# sbcs.net
KiCad netlist of a schematic drawn in Altium Designer
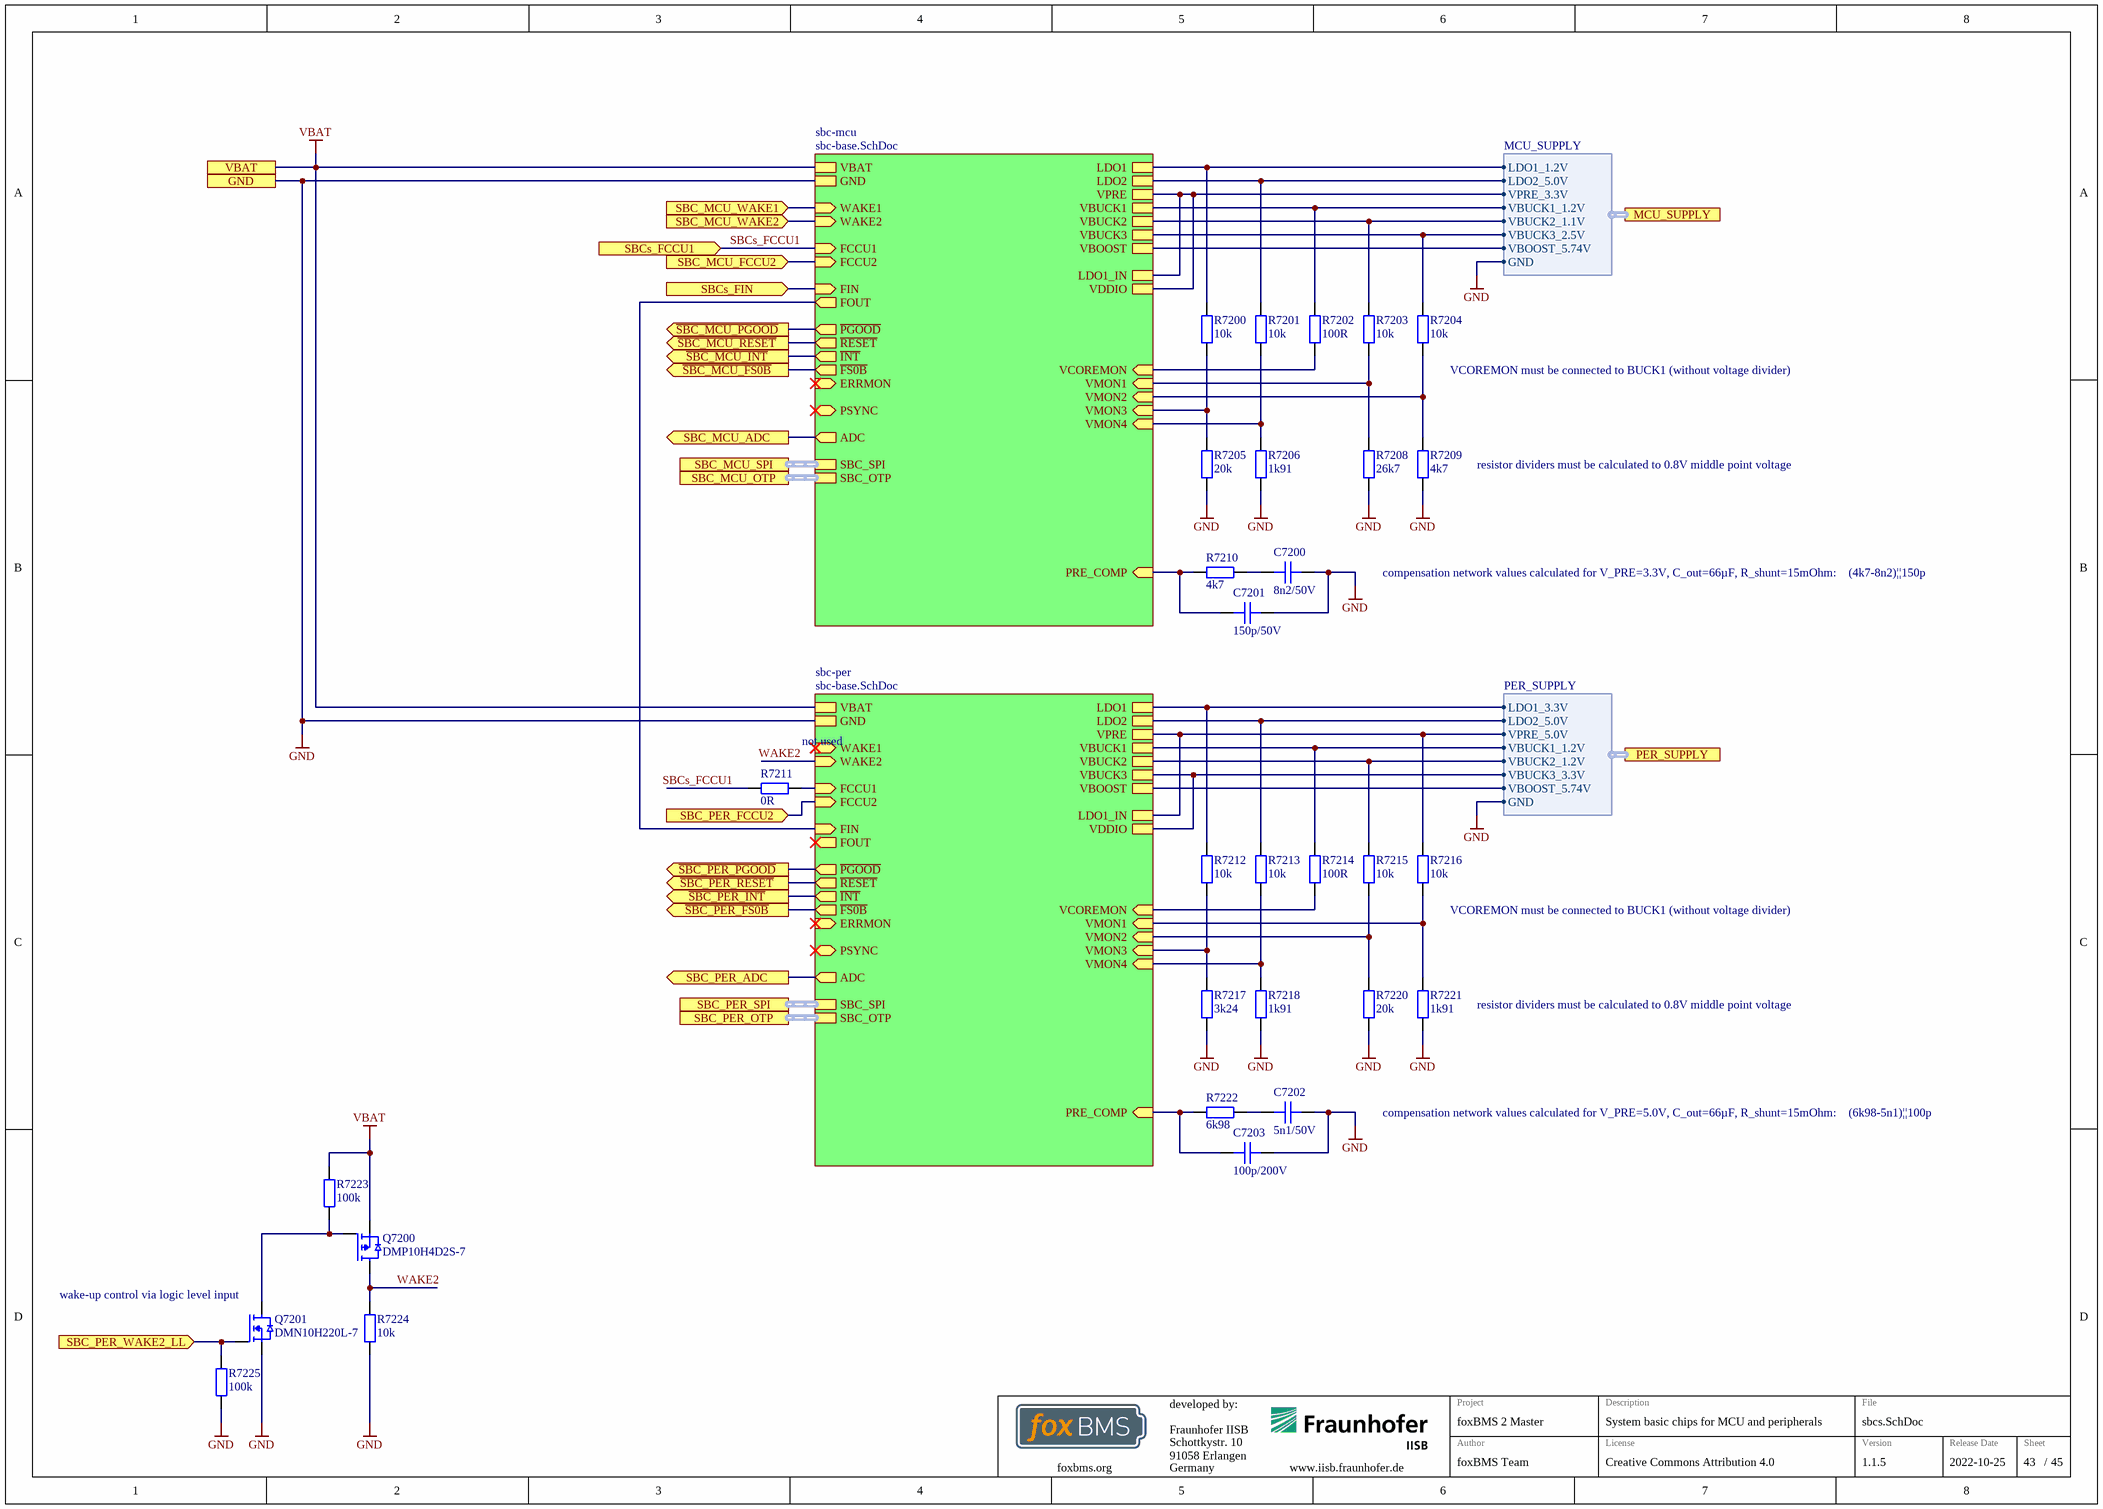
[diagram p0: sbcs.SchDoc]

(export (version "E")
  (design (tool "Eeschema 10.0.6"))
  (components
    (comp (ref "C7200")
      (value "8n2/50V")
      (footprint "CAPC1608X08N")
      (description "MLCC")
      (fields (field (name "PART NUMBER") "gen_C_ceramic_8n2_50V_C0G_0603"))
      (libsource (lib "OE750") (part "C"))
    )
    (comp (ref "C7201")
      (value "150p/50V")
      (footprint "CAPC1005X06N")
      (description "MLCC")
      (fields (field (name "PART NUMBER") "gen_C_ceramic_150p_50V_C0G_0402"))
      (libsource (lib "OE750") (part "C"))
    )
    (comp (ref "C7202")
      (value "5n1/50V")
      (footprint "CAPC1608X08N")
      (description "MLCC")
      (fields (field (name "PART NUMBER") "gen_C_ceramic_5n1_50V_C0G_0603"))
      (libsource (lib "OE750") (part "C"))
    )
    (comp (ref "C7203")
      (value "100p/200V")
      (footprint "CAPC1005X06N")
      (description "MLCC")
      (fields (field (name "PART NUMBER") "gen_C_ceramic_100p_200V_C0G_0402") (field (name "TOLERANCE") "5%"))
      (libsource (lib "OE750") (part "C"))
    )
    (comp (ref "Q7200")
      (value "DMP10H4D2S-7")
      (footprint "SOT95P237X110-3N")
      (description "MOSFET-Transistor, p-Kanal, 0.27 A, 100 V, 4.2 ohm")
      (fields (field (name "MANUFACTURER") "Diodes"))
      (libsource (lib "OE750") (part "PMOS"))
    )
    (comp (ref "Q7201")
      (value "DMN10H220L-7")
      (footprint "SOT95P237X110-3N")
      (description "MOSFET-Transistor, n-Kanal, 1.6 A, 100 V, 0.250 ohm")
      (fields (field (name "MANUFACTURER") "Diodes"))
      (libsource (lib "OE750") (part "NMOS"))
    )
    (comp (ref "R7200")
      (value "10k")
      (footprint "RESC1005X04N")
      (description "SMD Resistor 10k 0402")
      (fields (field (name "PART NUMBER") "gen_R_10k_0402") (field (name "TOLERANCE") "1%"))
      (libsource (lib "OE750") (part "R"))
    )
    (comp (ref "R7201")
      (value "10k")
      (footprint "RESC1005X04N")
      (description "SMD Resistor 10k 0402")
      (fields (field (name "PART NUMBER") "gen_R_10k_0402") (field (name "TOLERANCE") "1%"))
      (libsource (lib "OE750") (part "R"))
    )
    (comp (ref "R7202")
      (value "100R")
      (footprint "RESC1005X04N")
      (description "SMD Resistor 100R 0402")
      (fields (field (name "PART NUMBER") "gen_R_100R_0402") (field (name "TOLERANCE") "1%"))
      (libsource (lib "OE750") (part "R"))
    )
    (comp (ref "R7203")
      (value "10k")
      (footprint "RESC1005X04N")
      (description "SMD Resistor 10k 0402")
      (fields (field (name "PART NUMBER") "gen_R_10k_0402") (field (name "TOLERANCE") "1%"))
      (libsource (lib "OE750") (part "R"))
    )
    (comp (ref "R7204")
      (value "10k")
      (footprint "RESC1005X04N")
      (description "SMD Resistor 10k 0402")
      (fields (field (name "PART NUMBER") "gen_R_10k_0402") (field (name "TOLERANCE") "1%"))
      (libsource (lib "OE750") (part "R"))
    )
    (comp (ref "R7205")
      (value "20k")
      (footprint "RESC1005X04N")
      (description "SMD Resistor 20k 0402")
      (fields (field (name "PART NUMBER") "gen_R_20k_0402") (field (name "TOLERANCE") "1%"))
      (libsource (lib "OE750") (part "R"))
    )
    (comp (ref "R7206")
      (value "1k91")
      (footprint "RESC1005X04N")
      (description "SMD Resistor 1k91 0402")
      (fields (field (name "PART NUMBER") "gen_R_1k91_0402") (field (name "TOLERANCE") "1%"))
      (libsource (lib "OE750") (part "R"))
    )
    (comp (ref "R7208")
      (value "26k7")
      (footprint "RESC1005X04N")
      (description "SMD Resistor 26k7 0402")
      (fields (field (name "PART NUMBER") "gen_R_26k7_0402") (field (name "TOLERANCE") "1%"))
      (libsource (lib "OE750") (part "R"))
    )
    (comp (ref "R7209")
      (value "4k7")
      (footprint "RESC1005X04N")
      (description "SMD Resistor 4k7 0402")
      (fields (field (name "PART NUMBER") "gen_R_4k7_0402") (field (name "TOLERANCE") "1%"))
      (libsource (lib "OE750") (part "R"))
    )
    (comp (ref "R7210")
      (value "4k7")
      (footprint "RESC1005X04N")
      (description "SMD Resistor 4k7 0402")
      (fields (field (name "PART NUMBER") "gen_R_4k7_0402") (field (name "TOLERANCE") "1%"))
      (libsource (lib "OE750") (part "R"))
    )
    (comp (ref "R7211")
      (value "0R")
      (footprint "RESC1005X04N")
      (description "SMD Resistor 0R 0402")
      (fields (field (name "PART NUMBER") "gen_R_0R_0402") (field (name "POWER") "0.063W"))
      (libsource (lib "OE750") (part "R"))
    )
    (comp (ref "R7212")
      (value "10k")
      (footprint "RESC1005X04N")
      (description "SMD Resistor 10k 0402")
      (fields (field (name "PART NUMBER") "gen_R_10k_0402") (field (name "TOLERANCE") "1%"))
      (libsource (lib "OE750") (part "R"))
    )
    (comp (ref "R7213")
      (value "10k")
      (footprint "RESC1005X04N")
      (description "SMD Resistor 10k 0402")
      (fields (field (name "PART NUMBER") "gen_R_10k_0402") (field (name "TOLERANCE") "1%"))
      (libsource (lib "OE750") (part "R"))
    )
    (comp (ref "R7214")
      (value "100R")
      (footprint "RESC1005X04N")
      (description "SMD Resistor 100R 0402")
      (fields (field (name "PART NUMBER") "gen_R_100R_0402") (field (name "TOLERANCE") "1%"))
      (libsource (lib "OE750") (part "R"))
    )
    (comp (ref "R7215")
      (value "10k")
      (footprint "RESC1005X04N")
      (description "SMD Resistor 10k 0402")
      (fields (field (name "PART NUMBER") "gen_R_10k_0402") (field (name "TOLERANCE") "1%"))
      (libsource (lib "OE750") (part "R"))
    )
    (comp (ref "R7216")
      (value "10k")
      (footprint "RESC1005X04N")
      (description "SMD Resistor 10k 0402")
      (fields (field (name "PART NUMBER") "gen_R_10k_0402") (field (name "TOLERANCE") "1%"))
      (libsource (lib "OE750") (part "R"))
    )
    (comp (ref "R7217")
      (value "3k24")
      (footprint "RESC1005X04N")
      (description "SMD Resistor 3k24 0402")
      (fields (field (name "PART NUMBER") "gen_R_3k24_0402") (field (name "TOLERANCE") "1%"))
      (libsource (lib "OE750") (part "R"))
    )
    (comp (ref "R7218")
      (value "1k91")
      (footprint "RESC1005X04N")
      (description "SMD Resistor 1k91 0402")
      (fields (field (name "PART NUMBER") "gen_R_1k91_0402") (field (name "TOLERANCE") "1%"))
      (libsource (lib "OE750") (part "R"))
    )
    (comp (ref "R7220")
      (value "20k")
      (footprint "RESC1005X04N")
      (description "SMD Resistor 20k 0402")
      (fields (field (name "PART NUMBER") "gen_R_20k_0402") (field (name "TOLERANCE") "1%"))
      (libsource (lib "OE750") (part "R"))
    )
    (comp (ref "R7221")
      (value "1k91")
      (footprint "RESC1005X04N")
      (description "SMD Resistor 1k91 0402")
      (fields (field (name "PART NUMBER") "gen_R_1k91_0402") (field (name "TOLERANCE") "1%"))
      (libsource (lib "OE750") (part "R"))
    )
    (comp (ref "R7222")
      (value "6k98")
      (footprint "RESC1005X04N")
      (description "SMD Resistor 6k98 0402")
      (fields (field (name "PART NUMBER") "gen_R_6k98_0402") (field (name "TOLERANCE") "1%"))
      (libsource (lib "OE750") (part "R"))
    )
    (comp (ref "R7223")
      (value "100k")
      (footprint "RESC1005X04N")
      (description "SMD Resistor 100k 0402")
      (fields (field (name "PART NUMBER") "gen_R_100k_0402") (field (name "TOLERANCE") "1%"))
      (libsource (lib "OE750") (part "R"))
    )
    (comp (ref "R7224")
      (value "10k")
      (footprint "RESC1005X04N")
      (description "SMD Resistor 10k 0402")
      (fields (field (name "PART NUMBER") "gen_R_10k_0402") (field (name "TOLERANCE") "1%"))
      (libsource (lib "OE750") (part "R"))
    )
    (comp (ref "R7225")
      (value "100k")
      (footprint "RESC1005X04N")
      (description "SMD Resistor 100k 0402")
      (fields (field (name "PART NUMBER") "gen_R_100k_0402") (field (name "TOLERANCE") "1%"))
      (libsource (lib "OE750") (part "R"))
    )
  )
  (nets
    (net (code "9") (name "/FCCU1") (class "Default")
      (node (ref "R7211") (pin "2") (pinfunction "2_2") (pintype "passive"))
    )
    (net (code "12") (name "/LDO1") (class "Default")
      (node (ref "R7212") (pin "2") (pinfunction "2_2") (pintype "passive"))
    )
    (net (code "13") (name "/LDO1_1") (class "Default")
      (node (ref "R7200") (pin "2") (pinfunction "2_2") (pintype "passive"))
    )
    (net (code "14") (name "/LDO1_IN") (class "Default")
      (node (ref "R7216") (pin "2") (pinfunction "2_2") (pintype "passive"))
    )
    (net (code "16") (name "/LDO2") (class "Default")
      (node (ref "R7213") (pin "2") (pinfunction "2_2") (pintype "passive"))
    )
    (net (code "17") (name "/LDO2_1") (class "Default")
      (node (ref "R7201") (pin "2") (pinfunction "2_2") (pintype "passive"))
    )
    (net (code "18") (name "/PRE_COMP") (class "Default")
      (node (ref "C7201") (pin "1") (pinfunction "1_1") (pintype "passive"))
      (node (ref "R7210") (pin "2") (pinfunction "2_2") (pintype "passive"))
    )
    (net (code "19") (name "/PRE_COMP_1") (class "Default")
      (node (ref "C7203") (pin "1") (pinfunction "1_1") (pintype "passive"))
      (node (ref "R7222") (pin "2") (pinfunction "2_2") (pintype "passive"))
    )
    (net (code "40") (name "/SBC_PER_WAKE2_LL") (class "Default")
      (node (ref "Q7201") (pin "G") (pinfunction "G_G") (pintype "passive"))
      (node (ref "R7225") (pin "1") (pinfunction "1_1") (pintype "passive"))
    )
    (net (code "41") (name "/SBCs_FCCU1") (class "Default")
      (node (ref "R7211") (pin "1") (pinfunction "1_1") (pintype "passive"))
    )
    (net (code "45") (name "/VBUCK1") (class "Default")
      (node (ref "R7214") (pin "2") (pinfunction "2_2") (pintype "passive"))
    )
    (net (code "46") (name "/VBUCK1_1") (class "Default")
      (node (ref "R7202") (pin "2") (pinfunction "2_2") (pintype "passive"))
    )
    (net (code "47") (name "/VBUCK2") (class "Default")
      (node (ref "R7215") (pin "2") (pinfunction "2_2") (pintype "passive"))
    )
    (net (code "48") (name "/VBUCK2_1") (class "Default")
      (node (ref "R7203") (pin "2") (pinfunction "2_2") (pintype "passive"))
    )
    (net (code "50") (name "/VBUCK3_1") (class "Default")
      (node (ref "R7204") (pin "2") (pinfunction "2_2") (pintype "passive"))
    )
    (net (code "51") (name "/VCOREMON") (class "Default")
      (node (ref "R7214") (pin "1") (pinfunction "1_1") (pintype "passive"))
    )
    (net (code "52") (name "/VCOREMON_1") (class "Default")
      (node (ref "R7202") (pin "1") (pinfunction "1_1") (pintype "passive"))
    )
    (net (code "53") (name "/VMON1") (class "Default")
      (node (ref "R7216") (pin "1") (pinfunction "1_1") (pintype "passive"))
      (node (ref "R7221") (pin "2") (pinfunction "2_2") (pintype "passive"))
    )
    (net (code "54") (name "/VMON1_1") (class "Default")
      (node (ref "R7203") (pin "1") (pinfunction "1_1") (pintype "passive"))
      (node (ref "R7208") (pin "2") (pinfunction "2_2") (pintype "passive"))
    )
    (net (code "55") (name "/VMON2") (class "Default")
      (node (ref "R7215") (pin "1") (pinfunction "1_1") (pintype "passive"))
      (node (ref "R7220") (pin "2") (pinfunction "2_2") (pintype "passive"))
    )
    (net (code "56") (name "/VMON2_1") (class "Default")
      (node (ref "R7204") (pin "1") (pinfunction "1_1") (pintype "passive"))
      (node (ref "R7209") (pin "2") (pinfunction "2_2") (pintype "passive"))
    )
    (net (code "57") (name "/VMON3") (class "Default")
      (node (ref "R7212") (pin "1") (pinfunction "1_1") (pintype "passive"))
      (node (ref "R7217") (pin "2") (pinfunction "2_2") (pintype "passive"))
    )
    (net (code "58") (name "/VMON3_1") (class "Default")
      (node (ref "R7200") (pin "1") (pinfunction "1_1") (pintype "passive"))
      (node (ref "R7205") (pin "2") (pinfunction "2_2") (pintype "passive"))
    )
    (net (code "59") (name "/VMON4") (class "Default")
      (node (ref "R7213") (pin "1") (pinfunction "1_1") (pintype "passive"))
      (node (ref "R7218") (pin "2") (pinfunction "2_2") (pintype "passive"))
    )
    (net (code "60") (name "/VMON4_1") (class "Default")
      (node (ref "R7201") (pin "1") (pinfunction "1_1") (pintype "passive"))
      (node (ref "R7206") (pin "2") (pinfunction "2_2") (pintype "passive"))
    )
    (net (code "62") (name "/WAKE2") (class "Default")
      (node (ref "Q7200") (pin "D") (pinfunction "D_D") (pintype "passive"))
      (node (ref "R7224") (pin "2") (pinfunction "2_2") (pintype "passive"))
    )
    (net (code "65") (name "GND") (class "Default")
      (node (ref "C7200") (pin "2") (pinfunction "2_2") (pintype "passive"))
      (node (ref "C7201") (pin "2") (pinfunction "2_2") (pintype "passive"))
      (node (ref "C7202") (pin "2") (pinfunction "2_2") (pintype "passive"))
      (node (ref "C7203") (pin "2") (pinfunction "2_2") (pintype "passive"))
      (node (ref "Q7201") (pin "S") (pinfunction "S_S") (pintype "passive"))
      (node (ref "R7205") (pin "1") (pinfunction "1_1") (pintype "passive"))
      (node (ref "R7206") (pin "1") (pinfunction "1_1") (pintype "passive"))
      (node (ref "R7208") (pin "1") (pinfunction "1_1") (pintype "passive"))
      (node (ref "R7209") (pin "1") (pinfunction "1_1") (pintype "passive"))
      (node (ref "R7217") (pin "1") (pinfunction "1_1") (pintype "passive"))
      (node (ref "R7218") (pin "1") (pinfunction "1_1") (pintype "passive"))
      (node (ref "R7220") (pin "1") (pinfunction "1_1") (pintype "passive"))
      (node (ref "R7221") (pin "1") (pinfunction "1_1") (pintype "passive"))
      (node (ref "R7224") (pin "1") (pinfunction "1_1") (pintype "passive"))
      (node (ref "R7225") (pin "2") (pinfunction "2_2") (pintype "passive"))
    )
    (net (code "66") (name "Net-(C7200-Pad1)") (class "Default")
      (node (ref "C7200") (pin "1") (pinfunction "1_1") (pintype "passive"))
      (node (ref "R7210") (pin "1") (pinfunction "1_1") (pintype "passive"))
    )
    (net (code "67") (name "Net-(C7202-Pad1)") (class "Default")
      (node (ref "C7202") (pin "1") (pinfunction "1_1") (pintype "passive"))
      (node (ref "R7222") (pin "1") (pinfunction "1_1") (pintype "passive"))
    )
    (net (code "68") (name "Net-(Q7200-PadG)") (class "Default")
      (node (ref "Q7200") (pin "G") (pinfunction "G_G") (pintype "passive"))
      (node (ref "Q7201") (pin "D") (pinfunction "D_D") (pintype "passive"))
      (node (ref "R7223") (pin "2") (pinfunction "2_2") (pintype "passive"))
    )
    (net (code "69") (name "VBAT") (class "Default")
      (node (ref "Q7200") (pin "S") (pinfunction "S_S") (pintype "passive"))
      (node (ref "R7223") (pin "1") (pinfunction "1_1") (pintype "passive"))
    )
  )
)
